# Earth_Connectors.net
KiCad netlist of a schematic drawn in Altium Designer
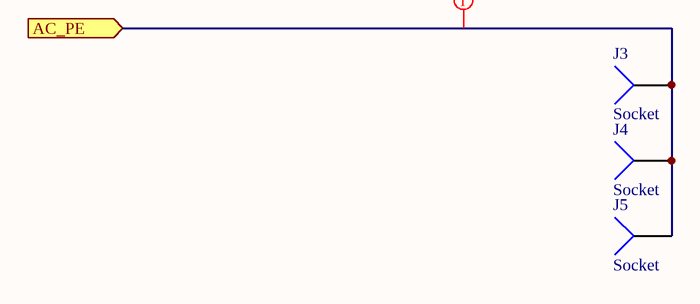
[diagram p0: Earth_Connectors.SchDoc]

(export (version "E")
  (design (tool "Eeschema 10.0.6"))
  (components
    (comp (ref "J3")
      (value "Socket")
      (footprint "PIN1")
      (fields (field (name "PUBLISHER") "Altium Limited"))
      (libsource (lib "Miscellaneous Connectors") (part "Socket"))
    )
    (comp (ref "J4")
      (value "Socket")
      (footprint "PIN1")
      (fields (field (name "PUBLISHER") "Altium Limited"))
      (libsource (lib "Miscellaneous Connectors") (part "Socket"))
    )
    (comp (ref "J5")
      (value "Socket")
      (footprint "PIN1")
      (fields (field (name "PUBLISHER") "Altium Limited"))
      (libsource (lib "Miscellaneous Connectors") (part "Socket"))
    )
  )
  (nets
    (net (code "1") (name "/AC_PE") (class "Default")
      (node (ref "J3") (pin "1") (pinfunction "1_1") (pintype "passive"))
      (node (ref "J4") (pin "1") (pinfunction "1_1") (pintype "passive"))
      (node (ref "J5") (pin "1") (pinfunction "1_1") (pintype "passive"))
    )
  )
)
